# Positive_Output.net
KiCad netlist of a schematic drawn in Altium Designer
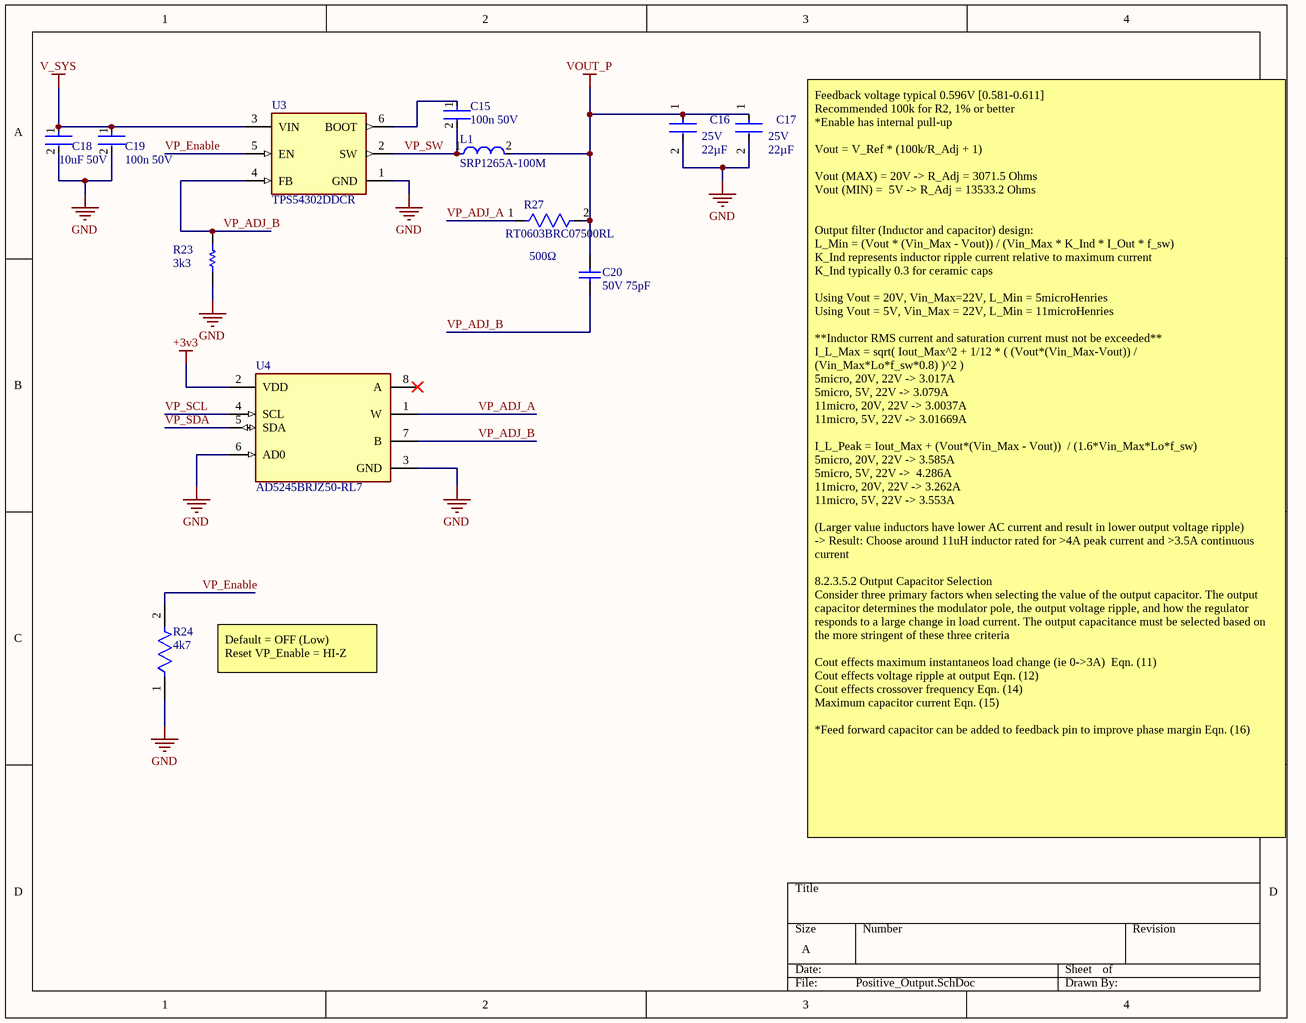
[diagram p0: Positive_Output.SchDoc]

(export (version "E")
  (design (tool "Eeschema 10.0.6"))
  (components
    (comp (ref "C15")
      (value "100n 50V")
      (footprint "FP-C0603C-CF-MFG")
      (description "CAP CER 0.1UF 50V X7R 0603")
      (fields (field (name "TOLERANCE") "0.1") (field (name "MANUFACTURER") "KEMET"))
      (libsource (lib "Altium Content Vault") (part "b4654b650e69147ec39a6b967a45e02"))
    )
    (comp (ref "C16")
      (value "CL31A226KAHNNNE")
      (footprint "CL31H-0_2_MFG")
      (fields (field (name "TOLERANCE") "10%"))
      (libsource (lib "Altium Content Vault") (part "fb88589c83559698c54462c48d907c3"))
    )
    (comp (ref "C17")
      (value "CL31A226KAHNNNE")
      (footprint "CL31H-0_2_MFG")
      (fields (field (name "TOLERANCE") "10%"))
      (libsource (lib "Altium Content Vault") (part "fb88589c83559698c54462c48d907c3"))
    )
    (comp (ref "C18")
      (value "10uF 50V")
      (footprint "FP-CL31-IPC_C")
      (description "CAP CER 10UF 50V X5R 1206")
      (fields (field (name "TOLERANCE") "10%") (field (name "MANUFACTURER") "Samsung"))
      (libsource (lib "Altium Content Vault") (part "11868f565c42a9108669ba33697ecf6"))
    )
    (comp (ref "C19")
      (value "100n 50V")
      (footprint "FP-C0603C-CF-MFG")
      (description "CAP CER 0.1UF 50V X7R 0603")
      (fields (field (name "TOLERANCE") "0.1") (field (name "MANUFACTURER") "KEMET"))
      (libsource (lib "Altium Content Vault") (part "b4654b650e69147ec39a6b967a45e02"))
    )
    (comp (ref "C20")
      (value "50V 75pF")
      (footprint "CAPC1608X90X35ML15T15")
      (fields
        (field (name "PART NUMBER") "06035A750JAT2A")
        (field (name "MANUFACTURER") "AVX Interconnect / Elco")
      )
      (libsource (lib "Altium Content Vault") (part "CAP"))
    )
    (comp (ref "L1")
      (value "SRP1265A-100M")
      (footprint "FP-SRP1265A-100M-MFG")
      (description "FIXED IND 10UH 10A 16.5 MOHM SMD")
      (fields (field (name "TOLERANCE") "20%"))
      (libsource (lib "Altium Content Vault") (part "725321dda6339637d4d059423bc1c3c"))
    )
    (comp (ref "R23")
      (value "3k3")
      (footprint "RESC0603(1608)_N")
      (description "100K 0.1W 1% 0603 (1608 Metric)  SMD")
      (fields (field (name "POWER") "0.1 W") (field (name "TOLERANCE") "1 %"))
      (libsource (lib "Altium Content Vault") (part "RES"))
    )
    (comp (ref "R24")
      (value "4k7")
      (footprint "FP-AC0603-IPC_A")
      (description "RES 4.7KΩ 1.00% 0.1W 0603")
      (fields (field (name "TOLERANCE") "1%"))
      (libsource (lib "Altium Content Vault") (part "1029c3af85768c4190bb7ad29bc67b5"))
    )
    (comp (ref "R27")
      (value "RT0603BRC07500RL")
      (footprint "RESC16080X45_RT0603-0_55_MFG")
      (description "Fixed Resistor, Thin Film, 0.1W, 500ohm, 75V, 0.1% +/-Tol, 15ppm/Cel, Surface Mount, 0603")
      (fields (field (name "TOLERANCE") "0.1%"))
      (libsource (lib "Altium Content Vault") (part "beb0a2e81d78bb8429d162089e89c6a"))
    )
    (comp (ref "U3")
      (value "TPS54302DDCR")
      (footprint "FP-DDC0006A-MFG")
      (description "IC REG BUCK ADJ 3A TSOT23-6")
      (fields
        (field (name "MANUFACTURER") "Texas Instruments")
        (field (name "OCTOPART") "https://octopart.com/tps54302ddcr-texas+instruments-74209025")
      )
      (libsource (lib "Altium Content Vault") (part "e6e62595b56d4ede9a2c24ebe42f01f"))
    )
    (comp (ref "U4")
      (value "AD5245BRJZ50-RL7")
      (footprint "FP-RJ-8-IPC_A")
      (description "IC DGT POT 50KOHM 256TAP SOT23-8")
      (fields (field (name "TOLERANCE") "30%"))
      (libsource (lib "Altium Content Vault") (part "c3d00f5cc55af6722170621c2373c9b"))
    )
  )
  (nets
    (net (code "1") (name "+3v3") (class "Default")
      (node (ref "U4") (pin "2") (pinfunction "VDD_2") (pintype "power_in"))
    )
    (net (code "2") (name "/VP_ADJ_A") (class "Default")
      (node (ref "R27") (pin "1") (pinfunction "1_1") (pintype "passive"))
      (node (ref "U4") (pin "1") (pinfunction "W_1") (pintype "passive"))
    )
    (net (code "3") (name "/VP_ADJ_B") (class "Default")
      (node (ref "C20") (pin "1") (pinfunction "1_1") (pintype "passive"))
      (node (ref "R23") (pin "2") (pinfunction "2_2") (pintype "passive"))
      (node (ref "U3") (pin "4") (pinfunction "FB_4") (pintype "input"))
      (node (ref "U4") (pin "7") (pinfunction "B_7") (pintype "passive"))
    )
    (net (code "4") (name "/VP_Enable") (class "Default")
      (node (ref "R24") (pin "2") (pinfunction "2_2") (pintype "passive"))
      (node (ref "U3") (pin "5") (pinfunction "EN_5") (pintype "input"))
    )
    (net (code "5") (name "/VP_SCL") (class "Default")
      (node (ref "U4") (pin "4") (pinfunction "SCL_4") (pintype "input"))
    )
    (net (code "6") (name "/VP_SDA") (class "Default")
      (node (ref "U4") (pin "5") (pinfunction "SDA_5") (pintype "bidirectional"))
    )
    (net (code "7") (name "/VP_SW") (class "Default")
      (node (ref "C15") (pin "2") (pinfunction "2_2") (pintype "passive"))
      (node (ref "L1") (pin "1") (pinfunction "1_1") (pintype "passive"))
      (node (ref "U3") (pin "2") (pinfunction "SW_2") (pintype "output"))
    )
    (net (code "8") (name "GND") (class "Default")
      (node (ref "C16") (pin "2") (pinfunction "2_2") (pintype "passive"))
      (node (ref "C17") (pin "2") (pinfunction "2_2") (pintype "passive"))
      (node (ref "C18") (pin "2") (pinfunction "2_2") (pintype "passive"))
      (node (ref "C19") (pin "2") (pinfunction "2_2") (pintype "passive"))
      (node (ref "R23") (pin "1") (pinfunction "1_1") (pintype "passive"))
      (node (ref "R24") (pin "1") (pinfunction "1_1") (pintype "passive"))
      (node (ref "U3") (pin "1") (pinfunction "GND_1") (pintype "power_in"))
      (node (ref "U4") (pin "3") (pinfunction "GND_3") (pintype "power_in"))
      (node (ref "U4") (pin "6") (pinfunction "AD0_6") (pintype "input"))
    )
    (net (code "9") (name "Net-(U3-BOOT)") (class "Default")
      (node (ref "C15") (pin "1") (pinfunction "1_1") (pintype "passive"))
      (node (ref "U3") (pin "6") (pinfunction "BOOT_6") (pintype "output"))
    )
    (net (code "10") (name "VOUT_P") (class "Default")
      (node (ref "C16") (pin "1") (pinfunction "1_1") (pintype "passive"))
      (node (ref "C17") (pin "1") (pinfunction "1_1") (pintype "passive"))
      (node (ref "C20") (pin "2") (pinfunction "2_2") (pintype "passive"))
      (node (ref "L1") (pin "2") (pinfunction "2_2") (pintype "passive"))
      (node (ref "R27") (pin "2") (pinfunction "2_2") (pintype "passive"))
    )
    (net (code "11") (name "V_SYS") (class "Default")
      (node (ref "C18") (pin "1") (pinfunction "1_1") (pintype "passive"))
      (node (ref "C19") (pin "1") (pinfunction "1_1") (pintype "passive"))
      (node (ref "U3") (pin "3") (pinfunction "VIN_3") (pintype "power_in"))
    )
    (net (code "12") (name "unconnected-(U4-A-Pad8)") (class "Default")
      (node (ref "U4") (pin "8") (pinfunction "A_8") (pintype "passive+no_connect"))
    )
  )
)
